# RGB_i2c_v3plusRTC.net
KiCad netlist of a schematic drawn in EAGLE
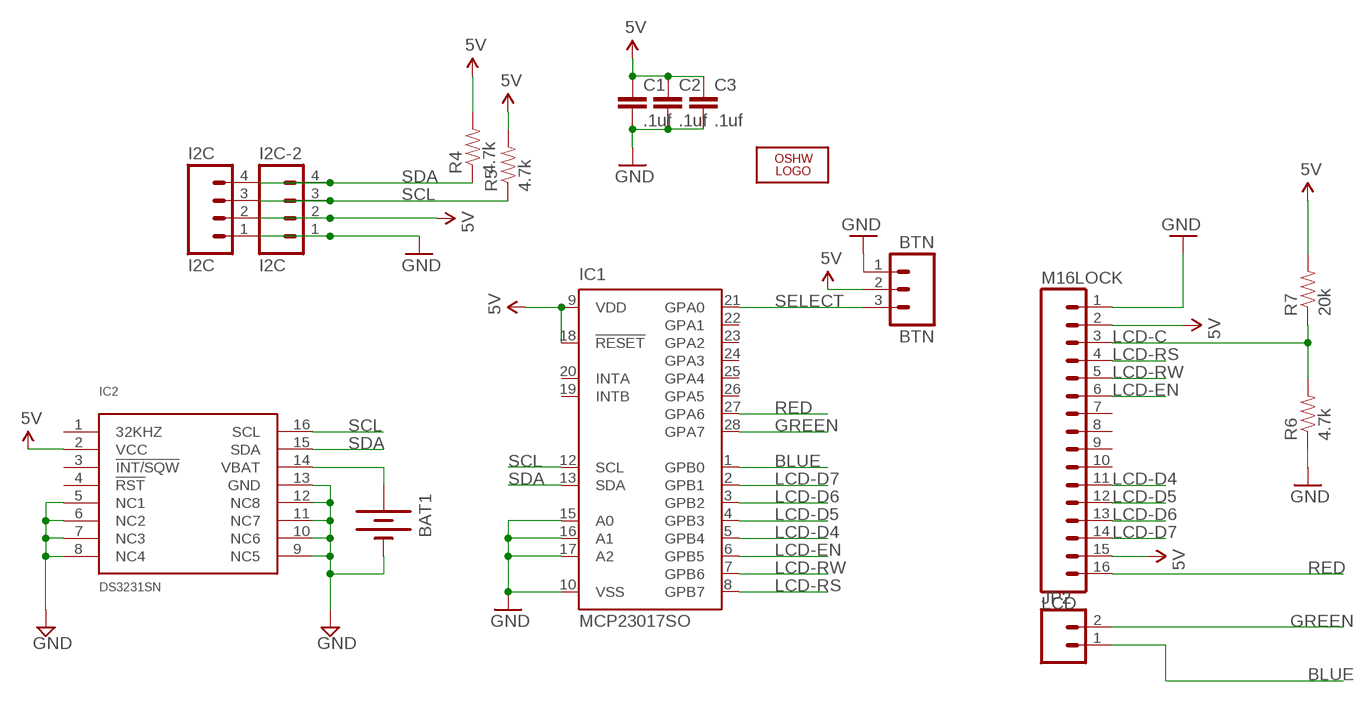
[diagram p0: schematic, sheet 1]

(export (version "E")
  (design (tool "Eeschema 10.0.6"))
  (components
    (comp (ref "BAT1")
      (value "BATTERY12MM")
      (footprint "eagle-import:BATTCON_12MM")
      (libsource (lib "eagle-import") (part "BATTERY12MM"))
    )
    (comp (ref "BTN")
      (value "BTN")
      (footprint "eagle-import:1X03_LOCK")
      (libsource (lib "eagle-import") (part "M03LOCK"))
    )
    (comp (ref "C1")
      (value ".1uf")
      (footprint "eagle-import:0805")
      (libsource (lib "eagle-import") (part "CAP0805"))
    )
    (comp (ref "C2")
      (value ".1uf")
      (footprint "eagle-import:0805")
      (libsource (lib "eagle-import") (part "CAP0805"))
    )
    (comp (ref "C3")
      (value ".1uf")
      (footprint "eagle-import:0805")
      (libsource (lib "eagle-import") (part "CAP0805"))
    )
    (comp (ref "I2C")
      (value "I2C")
      (footprint "eagle-import:1X04_LOCK")
      (libsource (lib "eagle-import") (part "M04LOCK"))
    )
    (comp (ref "I2C-2")
      (value "I2C")
      (footprint "eagle-import:1X04_LOCK")
      (libsource (lib "eagle-import") (part "M04LOCK"))
    )
    (comp (ref "IC1")
      (value "MCP23017SO")
      (footprint "eagle-import:SO28W")
      (libsource (lib "eagle-import") (part "MCP23017SO"))
    )
    (comp (ref "IC2")
      (value "DS3231SN")
      (footprint "eagle-import:SO16W")
      (libsource (lib "eagle-import") (part "DS3231SN"))
    )
    (comp (ref "JP2")
      (value "M02PTH")
      (footprint "eagle-import:1X02")
      (libsource (lib "eagle-import") (part "M02PTH"))
    )
    (comp (ref "LCD")
      (value "M16LOCK")
      (footprint "eagle-import:1X16_LOCK")
      (libsource (lib "eagle-import") (part "M16LOCK"))
    )
    (comp (ref "LOGO2")
      (value "OSHW_LOGO_10MILX0350-NT")
      (footprint "eagle-import:OSHW_10X350_NOTEXT")
      (libsource (lib "eagle-import") (part "OSHW_LOGO_10MILX0350-NT"))
    )
    (comp (ref "R4")
      (value "4.7k")
      (footprint "eagle-import:0805")
      (libsource (lib "eagle-import") (part "RESISTOR0805-RES"))
    )
    (comp (ref "R5")
      (value "4.7k")
      (footprint "eagle-import:0805")
      (libsource (lib "eagle-import") (part "RESISTOR0805-RES"))
    )
    (comp (ref "R6")
      (value "4.7k")
      (footprint "eagle-import:0805")
      (libsource (lib "eagle-import") (part "RESISTOR0805-RES"))
    )
    (comp (ref "R7")
      (value "20k")
      (footprint "eagle-import:0805")
      (libsource (lib "eagle-import") (part "RESISTOR0805-RES"))
    )
  )
  (nets
    (net (code "1") (name "/BLUE") (class "Default")
      (node (ref "IC1") (pin "1") (pinfunction "GPB0_1") (pintype "bidirectional"))
      (node (ref "JP2") (pin "1") (pinfunction "1_1") (pintype "passive"))
    )
    (net (code "2") (name "/GREEN") (class "Default")
      (node (ref "IC1") (pin "28") (pinfunction "GPA7_28") (pintype "bidirectional"))
      (node (ref "JP2") (pin "2") (pinfunction "2_2") (pintype "passive"))
    )
    (net (code "3") (name "/LCD-C") (class "Default")
      (node (ref "LCD") (pin "3") (pinfunction "3_3") (pintype "passive"))
      (node (ref "R6") (pin "2") (pinfunction "2_2") (pintype "passive"))
      (node (ref "R7") (pin "1") (pinfunction "1_1") (pintype "passive"))
    )
    (net (code "4") (name "/LCD-D4") (class "Default")
      (node (ref "IC1") (pin "5") (pinfunction "GPB4_5") (pintype "bidirectional"))
      (node (ref "LCD") (pin "11") (pinfunction "11_11") (pintype "passive"))
    )
    (net (code "5") (name "/LCD-D5") (class "Default")
      (node (ref "IC1") (pin "4") (pinfunction "GPB3_4") (pintype "bidirectional"))
      (node (ref "LCD") (pin "12") (pinfunction "12_12") (pintype "passive"))
    )
    (net (code "6") (name "/LCD-D6") (class "Default")
      (node (ref "IC1") (pin "3") (pinfunction "GPB2_3") (pintype "bidirectional"))
      (node (ref "LCD") (pin "13") (pinfunction "13_13") (pintype "passive"))
    )
    (net (code "7") (name "/LCD-D7") (class "Default")
      (node (ref "IC1") (pin "2") (pinfunction "GPB1_2") (pintype "bidirectional"))
      (node (ref "LCD") (pin "14") (pinfunction "14_14") (pintype "passive"))
    )
    (net (code "8") (name "/LCD-EN") (class "Default")
      (node (ref "IC1") (pin "6") (pinfunction "GPB5_6") (pintype "bidirectional"))
      (node (ref "LCD") (pin "6") (pinfunction "6_6") (pintype "passive"))
    )
    (net (code "9") (name "/LCD-RS") (class "Default")
      (node (ref "IC1") (pin "8") (pinfunction "GPB7_8") (pintype "bidirectional"))
      (node (ref "LCD") (pin "4") (pinfunction "4_4") (pintype "passive"))
    )
    (net (code "10") (name "/LCD-RW") (class "Default")
      (node (ref "IC1") (pin "7") (pinfunction "GPB6_7") (pintype "bidirectional"))
      (node (ref "LCD") (pin "5") (pinfunction "5_5") (pintype "passive"))
    )
    (net (code "11") (name "/RED") (class "Default")
      (node (ref "IC1") (pin "27") (pinfunction "GPA6_27") (pintype "bidirectional"))
      (node (ref "LCD") (pin "16") (pinfunction "16_16") (pintype "passive"))
    )
    (net (code "12") (name "/SCL") (class "Default")
      (node (ref "I2C") (pin "3") (pinfunction "3_3") (pintype "passive"))
      (node (ref "I2C-2") (pin "3") (pinfunction "3_3") (pintype "passive"))
      (node (ref "IC1") (pin "12") (pinfunction "SCL_12") (pintype "input"))
      (node (ref "IC2") (pin "16") (pinfunction "SCL_16") (pintype "bidirectional"))
      (node (ref "R5") (pin "1") (pinfunction "1_1") (pintype "passive"))
    )
    (net (code "13") (name "/SDA") (class "Default")
      (node (ref "I2C") (pin "4") (pinfunction "4_4") (pintype "passive"))
      (node (ref "I2C-2") (pin "4") (pinfunction "4_4") (pintype "passive"))
      (node (ref "IC1") (pin "13") (pinfunction "SDA_13") (pintype "bidirectional"))
      (node (ref "IC2") (pin "15") (pinfunction "SDA_15") (pintype "bidirectional"))
      (node (ref "R4") (pin "1") (pinfunction "1_1") (pintype "passive"))
    )
    (net (code "14") (name "/SELECT") (class "Default")
      (node (ref "BTN") (pin "3") (pinfunction "3_3") (pintype "passive"))
      (node (ref "IC1") (pin "21") (pinfunction "GPA0_21") (pintype "bidirectional"))
    )
    (net (code "15") (name "5V") (class "Default")
      (node (ref "BTN") (pin "2") (pinfunction "2_2") (pintype "passive"))
      (node (ref "C1") (pin "1") (pinfunction "1_1") (pintype "passive"))
      (node (ref "C2") (pin "1") (pinfunction "1_1") (pintype "passive"))
      (node (ref "C3") (pin "1") (pinfunction "1_1") (pintype "passive"))
      (node (ref "I2C") (pin "2") (pinfunction "2_2") (pintype "passive"))
      (node (ref "I2C-2") (pin "2") (pinfunction "2_2") (pintype "passive"))
      (node (ref "IC1") (pin "18") (pinfunction "~{RESET}_18") (pintype "input"))
      (node (ref "IC1") (pin "9") (pinfunction "VDD_9") (pintype "power_in"))
      (node (ref "IC2") (pin "2") (pinfunction "VCC_2") (pintype "bidirectional"))
      (node (ref "LCD") (pin "15") (pinfunction "15_15") (pintype "passive"))
      (node (ref "LCD") (pin "2") (pinfunction "2_2") (pintype "passive"))
      (node (ref "R4") (pin "2") (pinfunction "2_2") (pintype "passive"))
      (node (ref "R5") (pin "2") (pinfunction "2_2") (pintype "passive"))
      (node (ref "R7") (pin "2") (pinfunction "2_2") (pintype "passive"))
    )
    (net (code "16") (name "GND") (class "Default")
      (node (ref "BAT1") (pin "GND") (pinfunction "-_GND") (pintype "power_in"))
      (node (ref "BTN") (pin "1") (pinfunction "1_1") (pintype "passive"))
      (node (ref "C1") (pin "2") (pinfunction "2_2") (pintype "passive"))
      (node (ref "C2") (pin "2") (pinfunction "2_2") (pintype "passive"))
      (node (ref "C3") (pin "2") (pinfunction "2_2") (pintype "passive"))
      (node (ref "I2C") (pin "1") (pinfunction "1_1") (pintype "passive"))
      (node (ref "I2C-2") (pin "1") (pinfunction "1_1") (pintype "passive"))
      (node (ref "IC1") (pin "10") (pinfunction "VSS_10") (pintype "power_in"))
      (node (ref "IC1") (pin "15") (pinfunction "A0_15") (pintype "input"))
      (node (ref "IC1") (pin "16") (pinfunction "A1_16") (pintype "input"))
      (node (ref "IC1") (pin "17") (pinfunction "A2_17") (pintype "input"))
      (node (ref "IC2") (pin "10") (pinfunction "NC6_10") (pintype "bidirectional"))
      (node (ref "IC2") (pin "11") (pinfunction "NC7_11") (pintype "bidirectional"))
      (node (ref "IC2") (pin "12") (pinfunction "NC8_12") (pintype "bidirectional"))
      (node (ref "IC2") (pin "13") (pinfunction "GND_13") (pintype "bidirectional"))
      (node (ref "IC2") (pin "5") (pinfunction "NC1_5") (pintype "bidirectional"))
      (node (ref "IC2") (pin "6") (pinfunction "NC2_6") (pintype "bidirectional"))
      (node (ref "IC2") (pin "7") (pinfunction "NC3_7") (pintype "bidirectional"))
      (node (ref "IC2") (pin "8") (pinfunction "NC4_8") (pintype "bidirectional"))
      (node (ref "IC2") (pin "9") (pinfunction "NC5_9") (pintype "bidirectional"))
      (node (ref "LCD") (pin "1") (pinfunction "1_1") (pintype "passive"))
      (node (ref "R6") (pin "1") (pinfunction "1_1") (pintype "passive"))
    )
    (net (code "17") (name "Net-(BAT1-+)") (class "Default")
      (node (ref "BAT1") (pin "PWR@1") (pinfunction "+_PWR@1") (pintype "power_in"))
      (node (ref "IC2") (pin "14") (pinfunction "VBAT_14") (pintype "bidirectional"))
    )
    (net (code "18") (name "unconnected-(IC1-GPA1-Pad22)") (class "Default")
      (node (ref "IC1") (pin "22") (pinfunction "GPA1_22") (pintype "bidirectional"))
    )
    (net (code "19") (name "unconnected-(IC1-GPA2-Pad23)") (class "Default")
      (node (ref "IC1") (pin "23") (pinfunction "GPA2_23") (pintype "bidirectional"))
    )
    (net (code "20") (name "unconnected-(IC1-GPA3-Pad24)") (class "Default")
      (node (ref "IC1") (pin "24") (pinfunction "GPA3_24") (pintype "bidirectional"))
    )
    (net (code "21") (name "unconnected-(IC1-GPA4-Pad25)") (class "Default")
      (node (ref "IC1") (pin "25") (pinfunction "GPA4_25") (pintype "bidirectional"))
    )
    (net (code "22") (name "unconnected-(IC1-GPA5-Pad26)") (class "Default")
      (node (ref "IC1") (pin "26") (pinfunction "GPA5_26") (pintype "bidirectional"))
    )
    (net (code "23") (name "unconnected-(IC1-INTA-Pad20)") (class "Default")
      (node (ref "IC1") (pin "20") (pinfunction "INTA_20") (pintype "output"))
    )
    (net (code "24") (name "unconnected-(IC1-INTB-Pad19)") (class "Default")
      (node (ref "IC1") (pin "19") (pinfunction "INTB_19") (pintype "output"))
    )
    (net (code "25") (name "unconnected-(IC2-32KHZ-Pad1)") (class "Default")
      (node (ref "IC2") (pin "1") (pinfunction "32KHZ_1") (pintype "bidirectional"))
    )
    (net (code "26") (name "unconnected-(IC2-~{INT{slash}SQW}-Pad3)") (class "Default")
      (node (ref "IC2") (pin "3") (pinfunction "~{INT/SQW}_3") (pintype "bidirectional"))
    )
    (net (code "27") (name "unconnected-(IC2-~{RST}-Pad4)") (class "Default")
      (node (ref "IC2") (pin "4") (pinfunction "~{RST}_4") (pintype "bidirectional"))
    )
    (net (code "28") (name "unconnected-(LCD-Pad7)") (class "Default")
      (node (ref "LCD") (pin "7") (pinfunction "7_7") (pintype "passive"))
    )
    (net (code "29") (name "unconnected-(LCD-Pad8)") (class "Default")
      (node (ref "LCD") (pin "8") (pinfunction "8_8") (pintype "passive"))
    )
    (net (code "30") (name "unconnected-(LCD-Pad9)") (class "Default")
      (node (ref "LCD") (pin "9") (pinfunction "9_9") (pintype "passive"))
    )
    (net (code "31") (name "unconnected-(LCD-Pad10)") (class "Default")
      (node (ref "LCD") (pin "10") (pinfunction "10_10") (pintype "passive"))
    )
  )
)
